# CW340_INPUT_POWER.net
KiCad netlist of a schematic drawn in Altium Designer
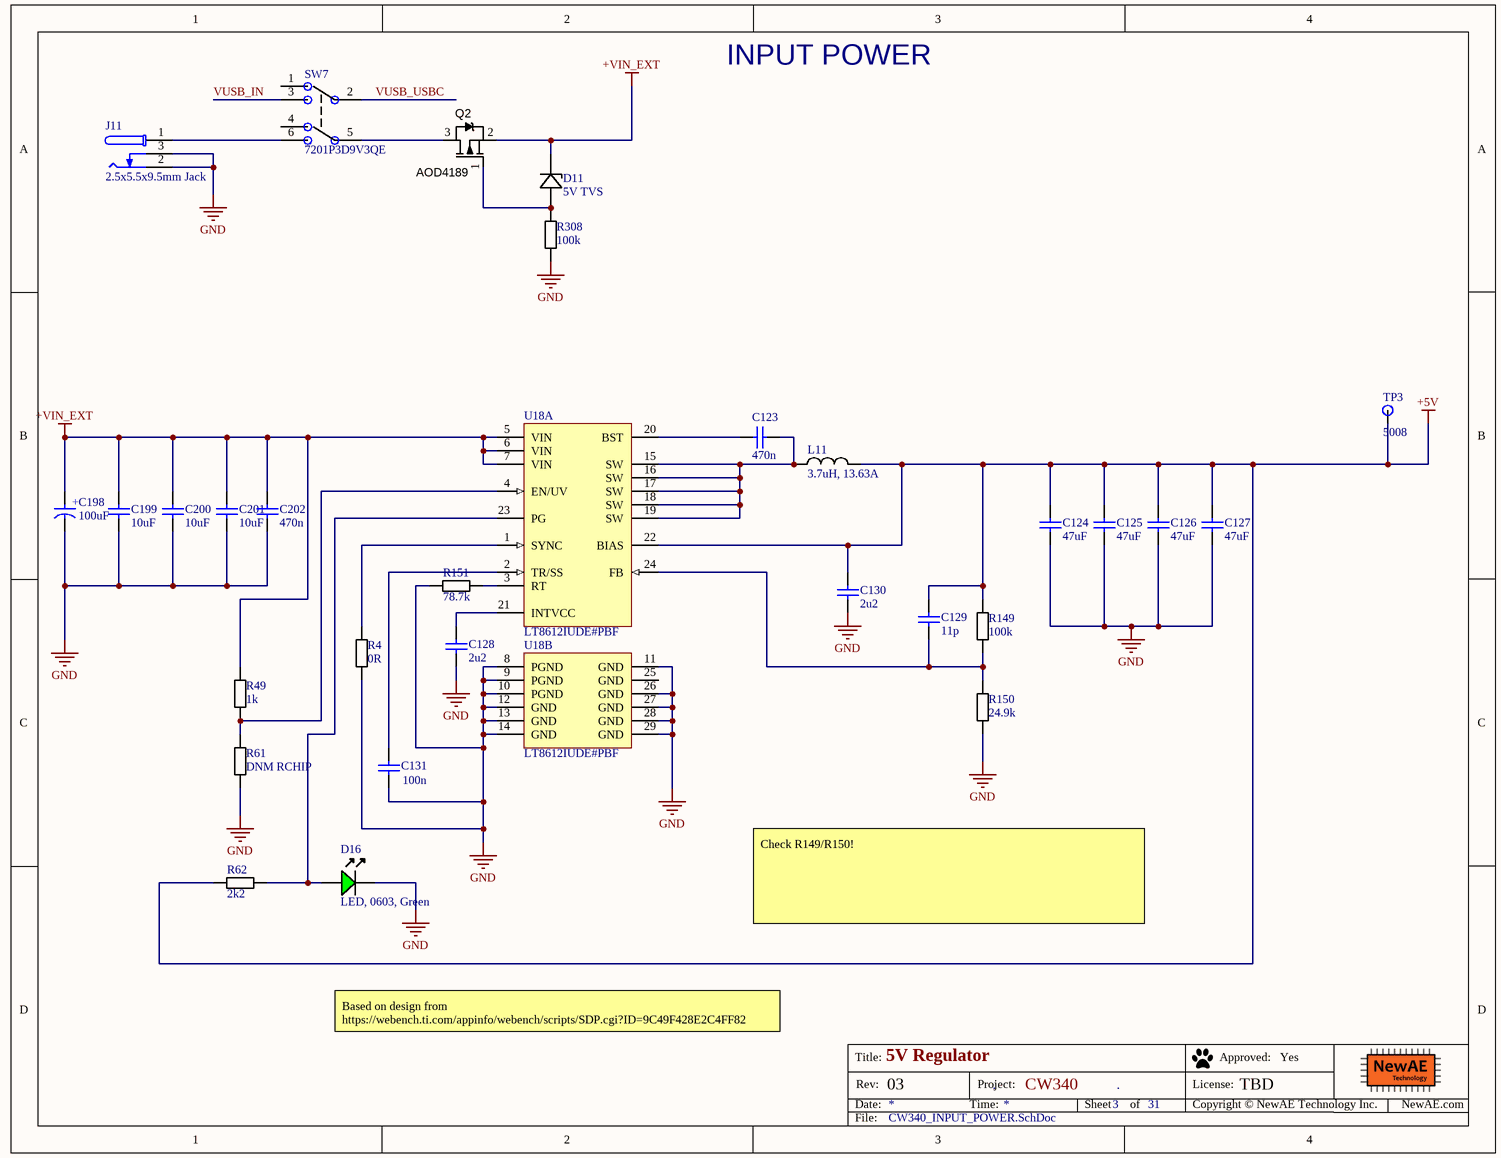
[diagram p0: CW340_INPUT_POWER.SchDoc]

(export (version "E")
  (design (tool "Eeschema 10.0.6"))
  (components
    (comp (ref "C123")
      (value "470n")
      (footprint "CAPC0603_M")
      (description "470n, 0603, 50V")
      (fields (field (name "PART NUMBER") "CCHIP-470n-0603-50V"))
      (libsource (lib "NewAE_AltiumLib") (part "CAP"))
    )
    (comp (ref "C124")
      (value "47uF")
      (footprint "CAPC3225X20N")
      (description "47u, 10V, 1210, Ceramic")
      (fields (field (name "PART NUMBER") "CCHIP-47u-1210") (field (name "TOLERANCE") "20%"))
      (libsource (lib "NewAE_AltiumLib") (part "CAP"))
    )
    (comp (ref "C125")
      (value "47uF")
      (footprint "CAPC3225X20N")
      (description "47u, 10V, 1210, Ceramic")
      (fields (field (name "PART NUMBER") "CCHIP-47u-1210") (field (name "TOLERANCE") "20%"))
      (libsource (lib "NewAE_AltiumLib") (part "CAP"))
    )
    (comp (ref "C126")
      (value "47uF")
      (footprint "CAPC3225X20N")
      (description "47u, 10V, 1210, Ceramic")
      (fields (field (name "PART NUMBER") "CCHIP-47u-1210") (field (name "TOLERANCE") "20%"))
      (libsource (lib "NewAE_AltiumLib") (part "CAP"))
    )
    (comp (ref "C127")
      (value "47uF")
      (footprint "CAPC3225X20N")
      (description "47u, 10V, 1210, Ceramic")
      (fields (field (name "PART NUMBER") "CCHIP-47u-1210") (field (name "TOLERANCE") "20%"))
      (libsource (lib "NewAE_AltiumLib") (part "CAP"))
    )
    (comp (ref "C128")
      (value "2u2")
      (footprint "CAPC0603_M")
      (description "2u2, 0603")
      (fields (field (name "PART NUMBER") "CCHIP-2u2-0603-16V"))
      (libsource (lib "NewAE_AltiumLib") (part "CAP"))
    )
    (comp (ref "C129")
      (value "11p")
      (footprint "RESC1608X55N")
      (description "CAP CER 11PF 50V C0G/NP0 0603")
      (fields (field (name "PART NUMBER") "CCHIP-11P-0603-50V") (field (name "TOLERANCE") "±5%"))
      (libsource (lib "NewAE_AltiumLib") (part "CAP"))
    )
    (comp (ref "C130")
      (value "2u2")
      (footprint "CAPC0603_M")
      (description "2u2, 0603")
      (fields (field (name "PART NUMBER") "CCHIP-2u2-0603"))
      (libsource (lib "NewAE_AltiumLib") (part "CAP"))
    )
    (comp (ref "C131")
      (value "100n")
      (footprint "CAPC0603_M")
      (description "100n, 0603")
      (fields (field (name "PART NUMBER") "CCHIP-100n-0603"))
      (libsource (lib "NewAE_AltiumLib") (part "CAP"))
    )
    (comp (ref "C198")
      (value "100uF")
      (footprint "CAP_AL_D6.3")
      (description "CAP ALUM 100UF 20% 35V RADIAL")
      (fields (field (name "PART NUMBER") "Cap_35v_100uF"))
      (libsource (lib "NewAE_AltiumLib") (part "CAP_POL"))
    )
    (comp (ref "C199")
      (value "10uF")
      (footprint "CAPC3225X20N")
      (description "10u, 50V, 1210, Ceramic")
      (fields (field (name "PART NUMBER") "CCHIP-10u-1210-50V") (field (name "TOLERANCE") "10%"))
      (libsource (lib "NewAE_AltiumLib") (part "CAP"))
    )
    (comp (ref "C200")
      (value "10uF")
      (footprint "CAPC3225X20N")
      (description "10u, 50V, 1210, Ceramic")
      (fields (field (name "PART NUMBER") "CCHIP-10u-1210-50V") (field (name "TOLERANCE") "10%"))
      (libsource (lib "NewAE_AltiumLib") (part "CAP"))
    )
    (comp (ref "C201")
      (value "10uF")
      (footprint "CAPC3225X20N")
      (description "10u, 50V, 1210, Ceramic")
      (fields (field (name "PART NUMBER") "CCHIP-10u-1210-50V") (field (name "TOLERANCE") "10%"))
      (libsource (lib "NewAE_AltiumLib") (part "CAP"))
    )
    (comp (ref "C202")
      (value "470n")
      (footprint "CAPC1206_M")
      (description "470n, 1206, 100V")
      (fields (field (name "PART NUMBER") "CCHIP-470n-1206-100V") (field (name "TOLERANCE") "10%"))
      (libsource (lib "NewAE_AltiumLib") (part "CAP"))
    )
    (comp (ref "D11")
      (value "5V TVS")
      (footprint "SOD-523")
      (description "TVS DIODE 1VSO 5VBD SOD523")
      (fields (field (name "PART NUMBER") "VESD05B1-02V-G3-08"))
      (libsource (lib "NewAE_AltiumLib") (part "TVS_DIODE_CATHODE_PIN1"))
    )
    (comp (ref "D16")
      (value "LED, 0603, Green")
      (footprint "LED-0603-GREEN")
      (description "Chip LED, Green")
      (fields (field (name "PART NUMBER") "LEDCHIP_0603_GREEN"))
      (libsource (lib "NewAE_AltiumLib") (part "LED_GREEN"))
    )
    (comp (ref "J11")
      (value "2.5x5.5x9.5mm Jack")
      (footprint "CUI_PJ-058BH")
      (description "CONN PWR JACK 2.5X5.5MM SOLDER")
      (fields (field (name "PART NUMBER") "CUI_PJ-058BH"))
      (libsource (lib "NewAE_AltiumLib") (part "DC_Jack_3PIN_NC"))
    )
    (comp (ref "L11")
      (value "3.7uH, 13.63A")
      (footprint "MLC1565 SERIES")
      (fields (field (name "PART NUMBER") "MLC1565-372MLB"))
      (libsource (lib "NewAE_AltiumLib") (part "IND"))
    )
    (comp (ref "Q2")
      (value "AOD4189")
      (footprint "DPAK_TO-252AA_M")
      (description "MOSFET P-CH 40V 40A TO252")
      (libsource (lib "NewAE_AltiumLib") (part "MOSFET_P_GSD"))
    )
    (comp (ref "R4")
      (value "0R")
      (footprint "RESC1005X40N")
      (fields (field (name "PART NUMBER") "RCHIP-0R-0402"))
      (libsource (lib "NewAE_AltiumLib") (part "RES-EU"))
    )
    (comp (ref "R49")
      (value "1k")
      (footprint "RESC1608X55N")
      (description "1k res, 0603, 1%, 1/10W")
      (fields (field (name "PART NUMBER") "RCHIP-1K-0603") (field (name "TOLERANCE") "1%"))
      (libsource (lib "") (part "RES-EU_1"))
    )
    (comp (ref "R61")
      (value "DNM RCHIP")
      (footprint "RESC1608X55N")
      (description "Do Not Mount Resistor")
      (fields (field (name "PART NUMBER") "RCHIP-DNM-0603"))
      (libsource (lib "") (part "RES-EU_1"))
    )
    (comp (ref "R62")
      (value "2k2")
      (footprint "RESC1608X55N")
      (description "2k2 res, 0603, 1%, 1/10W")
      (fields (field (name "PART NUMBER") "RCHIP-2K2-0603") (field (name "TOLERANCE") "1%"))
      (libsource (lib "") (part "RES-EU_2"))
    )
    (comp (ref "R149")
      (value "100k")
      (footprint "RESC1608X55N")
      (description "100k res, 0603, 1%, 1/10W")
      (fields (field (name "PART NUMBER") "RCHIP-100K-0603") (field (name "TOLERANCE") "1%"))
      (libsource (lib "") (part "RES-EU_1"))
    )
    (comp (ref "R150")
      (value "24.9k")
      (footprint "RESC1608X55N")
      (description "24k9 res, 0603, 1%, 1/10W")
      (fields (field (name "PART NUMBER") "RCHIP-24K9-0603") (field (name "TOLERANCE") "1%"))
      (libsource (lib "") (part "RES-EU_1"))
    )
    (comp (ref "R151")
      (value "78.7k")
      (footprint "RESC1608X55N")
      (description "78k7 res, 0603, 1%, 1/10W")
      (fields (field (name "PART NUMBER") "RCHIP-78k7-0603") (field (name "TOLERANCE") "1%"))
      (libsource (lib "") (part "RES-EU_2"))
    )
    (comp (ref "R308")
      (value "100k")
      (footprint "RESC1608X55N")
      (description "100k res, 0603, 1%, 1/10W")
      (fields (field (name "PART NUMBER") "RCHIP-100K-0603") (field (name "TOLERANCE") "1%"))
      (libsource (lib "") (part "RES-EU_1"))
    )
    (comp (ref "SW7")
      (value "7201P3D9V3QE")
      (footprint "7201P3D9V3QE")
      (description "DPDT, Switch, TH")
      (libsource (lib "NewAE_AltiumLib") (part "SW_DPDT_2MH"))
    )
    (comp (ref "TP3")
      (value "5008")
      (footprint "KEYSTONE5008")
      (description "TEST POINT PC COMPACT .063\"D ORG")
      (fields (field (name "PART NUMBER") "KEYSTONE_5008"))
      (libsource (lib "NewAE_AltiumLib") (part "KEYSTONE_5008"))
    )
    (comp (ref "U18")
      (value "LT8612IUDE#PBF")
      (footprint "LT-UDE-28_V")
      (description "Synchronous Step-Down Regulator, 3.4 to 42 V, -40 to 125 degC, 28-Pin PQFN (UDE), RoHS, Tube")
      (fields (field (name "MANUFACTURER") "Linear Technology"))
      (libsource (lib "Altium Content Vault") (part "LT-LT8612-28"))
    )
  )
  (nets
    (net (code "1") (name "+5V") (class "Default")
      (node (ref "C124") (pin "1") (pinfunction "1_1") (pintype "passive"))
      (node (ref "C125") (pin "1") (pinfunction "1_1") (pintype "passive"))
      (node (ref "C126") (pin "1") (pinfunction "1_1") (pintype "passive"))
      (node (ref "C127") (pin "1") (pinfunction "1_1") (pintype "passive"))
      (node (ref "C129") (pin "1") (pinfunction "1_1") (pintype "passive"))
      (node (ref "C130") (pin "1") (pinfunction "1_1") (pintype "passive"))
      (node (ref "L11") (pin "2") (pinfunction "2_2") (pintype "passive"))
      (node (ref "R149") (pin "1") (pinfunction "1_1") (pintype "passive"))
      (node (ref "R62") (pin "1") (pinfunction "1_1") (pintype "passive"))
      (node (ref "TP3") (pin "1") (pinfunction "1_1") (pintype "passive"))
      (node (ref "U18") (pin "22") (pinfunction "BIAS_22") (pintype "power_in"))
    )
    (net (code "2") (name "+VIN_EXT") (class "Default")
      (node (ref "C198") (pin "1") (pinfunction "1_1") (pintype "passive"))
      (node (ref "C199") (pin "1") (pinfunction "1_1") (pintype "passive"))
      (node (ref "C200") (pin "1") (pinfunction "1_1") (pintype "passive"))
      (node (ref "C201") (pin "1") (pinfunction "1_1") (pintype "passive"))
      (node (ref "C202") (pin "1") (pinfunction "1_1") (pintype "passive"))
      (node (ref "D11") (pin "1") (pinfunction "K_1") (pintype "passive"))
      (node (ref "Q2") (pin "2") (pinfunction "S_2") (pintype "passive"))
      (node (ref "R49") (pin "1") (pinfunction "1_1") (pintype "passive"))
      (node (ref "U18") (pin "5") (pinfunction "VIN_5") (pintype "power_in"))
      (node (ref "U18") (pin "6") (pinfunction "VIN_6") (pintype "power_in"))
      (node (ref "U18") (pin "7") (pinfunction "VIN_7") (pintype "power_in"))
    )
    (net (code "3") (name "/VUSB_IN") (class "Default")
      (node (ref "SW7") (pin "3") (pinfunction "IN_3") (pintype "passive"))
    )
    (net (code "4") (name "/VUSB_USBC") (class "Default")
      (node (ref "SW7") (pin "2") (pinfunction "IN_2") (pintype "passive"))
    )
    (net (code "5") (name "GND") (class "Default")
      (node (ref "C124") (pin "2") (pinfunction "2_2") (pintype "passive"))
      (node (ref "C125") (pin "2") (pinfunction "2_2") (pintype "passive"))
      (node (ref "C126") (pin "2") (pinfunction "2_2") (pintype "passive"))
      (node (ref "C127") (pin "2") (pinfunction "2_2") (pintype "passive"))
      (node (ref "C128") (pin "2") (pinfunction "2_2") (pintype "passive"))
      (node (ref "C130") (pin "2") (pinfunction "2_2") (pintype "passive"))
      (node (ref "C131") (pin "2") (pinfunction "2_2") (pintype "passive"))
      (node (ref "C198") (pin "2") (pinfunction "2_2") (pintype "passive"))
      (node (ref "C199") (pin "2") (pinfunction "2_2") (pintype "passive"))
      (node (ref "C200") (pin "2") (pinfunction "2_2") (pintype "passive"))
      (node (ref "C201") (pin "2") (pinfunction "2_2") (pintype "passive"))
      (node (ref "C202") (pin "2") (pinfunction "2_2") (pintype "passive"))
      (node (ref "D16") (pin "K") (pinfunction "K_K") (pintype "passive"))
      (node (ref "J11") (pin "2") (pinfunction "2_2") (pintype "passive"))
      (node (ref "J11") (pin "3") (pinfunction "3_3") (pintype "passive"))
      (node (ref "R150") (pin "2") (pinfunction "2_2") (pintype "passive"))
      (node (ref "R151") (pin "1") (pinfunction "1_1") (pintype "passive"))
      (node (ref "R308") (pin "2") (pinfunction "2_2") (pintype "passive"))
      (node (ref "R4") (pin "1") (pinfunction "1_1") (pintype "passive"))
      (node (ref "R61") (pin "2") (pinfunction "2_2") (pintype "passive"))
      (node (ref "U18") (pin "10") (pinfunction "PGND_10") (pintype "power_in"))
      (node (ref "U18") (pin "11") (pinfunction "GND_11") (pintype "power_in"))
      (node (ref "U18") (pin "12") (pinfunction "GND_12") (pintype "power_in"))
      (node (ref "U18") (pin "13") (pinfunction "GND_13") (pintype "power_in"))
      (node (ref "U18") (pin "14") (pinfunction "GND_14") (pintype "power_in"))
      (node (ref "U18") (pin "26") (pinfunction "GND_26") (pintype "power_in"))
      (node (ref "U18") (pin "27") (pinfunction "GND_27") (pintype "power_in"))
      (node (ref "U18") (pin "28") (pinfunction "GND_28") (pintype "power_in"))
      (node (ref "U18") (pin "29") (pinfunction "GND_29") (pintype "power_in"))
      (node (ref "U18") (pin "8") (pinfunction "PGND_8") (pintype "power_in"))
      (node (ref "U18") (pin "9") (pinfunction "PGND_9") (pintype "power_in"))
    )
    (net (code "6") (name "Net-(C123-Pad2)") (class "Default")
      (node (ref "C123") (pin "2") (pinfunction "2_2") (pintype "passive"))
      (node (ref "L11") (pin "1") (pinfunction "1_1") (pintype "passive"))
      (node (ref "U18") (pin "15") (pinfunction "SW_15") (pintype "power_in"))
      (node (ref "U18") (pin "16") (pinfunction "SW_16") (pintype "power_in"))
      (node (ref "U18") (pin "17") (pinfunction "SW_17") (pintype "power_in"))
      (node (ref "U18") (pin "18") (pinfunction "SW_18") (pintype "power_in"))
      (node (ref "U18") (pin "19") (pinfunction "SW_19") (pintype "power_in"))
    )
    (net (code "7") (name "Net-(D11-A)") (class "Default")
      (node (ref "D11") (pin "2") (pinfunction "A_2") (pintype "passive"))
      (node (ref "Q2") (pin "1") (pinfunction "G_1") (pintype "passive"))
      (node (ref "R308") (pin "1") (pinfunction "1_1") (pintype "passive"))
    )
    (net (code "8") (name "Net-(J11-Pad1)") (class "Default")
      (node (ref "J11") (pin "1") (pinfunction "1_1") (pintype "passive"))
      (node (ref "SW7") (pin "6") (pinfunction "IN_6") (pintype "passive"))
    )
    (net (code "9") (name "Net-(Q2-D)") (class "Default")
      (node (ref "Q2") (pin "3") (pinfunction "D_3") (pintype "passive"))
      (node (ref "SW7") (pin "5") (pinfunction "IN_5") (pintype "passive"))
    )
    (net (code "10") (name "Net-(U18A-BST)") (class "Default")
      (node (ref "C123") (pin "1") (pinfunction "1_1") (pintype "passive"))
      (node (ref "U18") (pin "20") (pinfunction "BST_20") (pintype "passive"))
    )
    (net (code "11") (name "Net-(U18A-EN{slash}UV)") (class "Default")
      (node (ref "R49") (pin "2") (pinfunction "2_2") (pintype "passive"))
      (node (ref "R61") (pin "1") (pinfunction "1_1") (pintype "passive"))
      (node (ref "U18") (pin "4") (pinfunction "EN/UV_4") (pintype "input"))
    )
    (net (code "12") (name "Net-(U18A-FB)") (class "Default")
      (node (ref "C129") (pin "2") (pinfunction "2_2") (pintype "passive"))
      (node (ref "R149") (pin "2") (pinfunction "2_2") (pintype "passive"))
      (node (ref "R150") (pin "1") (pinfunction "1_1") (pintype "passive"))
      (node (ref "U18") (pin "24") (pinfunction "FB_24") (pintype "input"))
    )
    (net (code "13") (name "Net-(U18A-INTVCC)") (class "Default")
      (node (ref "C128") (pin "1") (pinfunction "1_1") (pintype "passive"))
      (node (ref "U18") (pin "21") (pinfunction "INTVCC_21") (pintype "power_in"))
    )
    (net (code "14") (name "Net-(U18A-PG)") (class "Default")
      (node (ref "D16") (pin "A") (pinfunction "A_A") (pintype "passive"))
      (node (ref "R62") (pin "2") (pinfunction "2_2") (pintype "passive"))
      (node (ref "U18") (pin "23") (pinfunction "PG_23") (pintype "tri_state"))
    )
    (net (code "15") (name "Net-(U18A-RT)") (class "Default")
      (node (ref "R151") (pin "2") (pinfunction "2_2") (pintype "passive"))
      (node (ref "U18") (pin "3") (pinfunction "RT_3") (pintype "passive"))
    )
    (net (code "16") (name "Net-(U18A-SYNC)") (class "Default")
      (node (ref "R4") (pin "2") (pinfunction "2_2") (pintype "passive"))
      (node (ref "U18") (pin "1") (pinfunction "SYNC_1") (pintype "input"))
    )
    (net (code "17") (name "Net-(U18A-TR{slash}SS)") (class "Default")
      (node (ref "C131") (pin "1") (pinfunction "1_1") (pintype "passive"))
      (node (ref "U18") (pin "2") (pinfunction "TR/SS_2") (pintype "input"))
    )
    (net (code "18") (name "unconnected-(SW7-IN-Pad1)") (class "Default")
      (node (ref "SW7") (pin "1") (pinfunction "IN_1") (pintype "passive"))
    )
    (net (code "19") (name "unconnected-(SW7-IN-Pad4)") (class "Default")
      (node (ref "SW7") (pin "4") (pinfunction "IN_4") (pintype "passive"))
    )
    (net (code "20") (name "unconnected-(U18B-GND-Pad25)") (class "Default")
      (node (ref "U18") (pin "25") (pinfunction "GND_25") (pintype "power_in"))
    )
  )
)
